# ESP_CAM_VVN.net
KiCad netlist of a schematic drawn in EAGLE
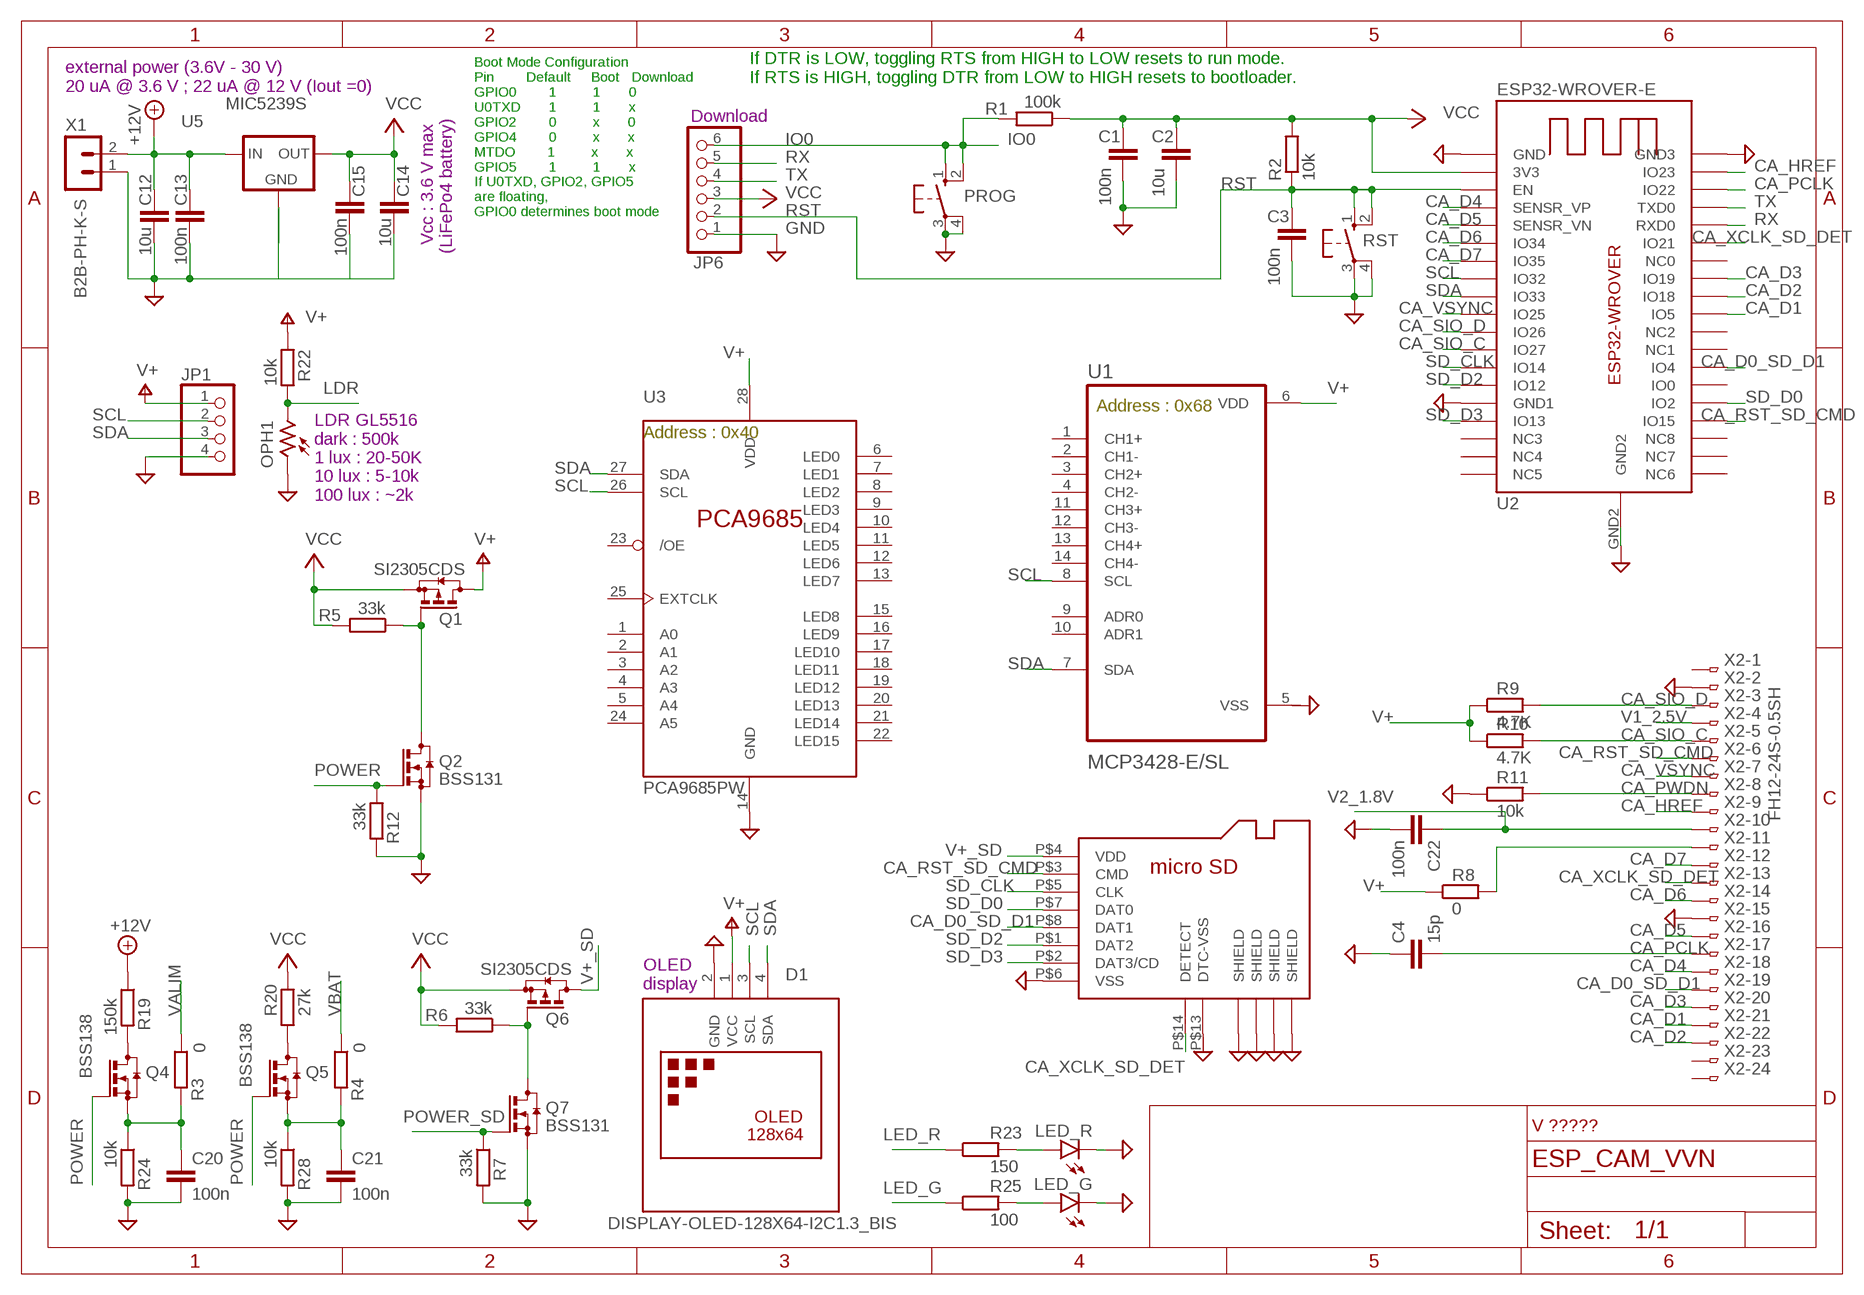
[diagram p0: schematic, sheet 1]

(export (version "E")
  (design (tool "Eeschema 10.0.6"))
  (components
    (comp (ref "C1")
      (value "100n")
      (footprint "eagle-import:C1206")
      (libsource (lib "eagle-import") (part "CC1206"))
    )
    (comp (ref "C2")
      (value "10u")
      (footprint "eagle-import:C1210")
      (libsource (lib "eagle-import") (part "CC1210"))
    )
    (comp (ref "C3")
      (value "100n")
      (footprint "eagle-import:C1206")
      (libsource (lib "eagle-import") (part "CC1206"))
    )
    (comp (ref "C4")
      (value "15p")
      (footprint "eagle-import:C1206")
      (libsource (lib "eagle-import") (part "CC1206"))
    )
    (comp (ref "C12")
      (value "10u")
      (footprint "eagle-import:C1210")
      (libsource (lib "eagle-import") (part "CC1210"))
    )
    (comp (ref "C13")
      (value "100n")
      (footprint "eagle-import:C1206")
      (libsource (lib "eagle-import") (part "CC1206"))
    )
    (comp (ref "C14")
      (value "10u")
      (footprint "eagle-import:C1210")
      (libsource (lib "eagle-import") (part "CC1210"))
    )
    (comp (ref "C15")
      (value "100n")
      (footprint "eagle-import:C1206")
      (libsource (lib "eagle-import") (part "CC1206"))
    )
    (comp (ref "C20")
      (value "100n")
      (footprint "eagle-import:C1206")
      (libsource (lib "eagle-import") (part "CC1206"))
    )
    (comp (ref "C21")
      (value "100n")
      (footprint "eagle-import:C1206")
      (libsource (lib "eagle-import") (part "CC1206"))
    )
    (comp (ref "C22")
      (value "100n")
      (footprint "eagle-import:C1206")
      (libsource (lib "eagle-import") (part "CC1206"))
    )
    (comp (ref "D1")
      (value "DISPLAY-OLED-128X64-I2C1.3_BIS")
      (footprint "eagle-import:DISPLAY-OLED-128X64-1.3-I2C_BIS")
      (libsource (lib "eagle-import") (part "DISPLAY-OLED-128X64-I2C1.3_BIS"))
    )
    (comp (ref "JP1")
      (value "PINHD-1X4")
      (footprint "eagle-import:1X04")
      (libsource (lib "eagle-import") (part "PINHD-1X4"))
    )
    (comp (ref "JP6")
      (value "PINHD-1X6")
      (footprint "eagle-import:1X06")
      (libsource (lib "eagle-import") (part "PINHD-1X6"))
    )
    (comp (ref "LED_G")
      (value "LEDSMT1206")
      (footprint "eagle-import:1206")
      (libsource (lib "eagle-import") (part "LEDSMT1206"))
    )
    (comp (ref "LED_R")
      (value "LEDSMT1206")
      (footprint "eagle-import:1206")
      (libsource (lib "eagle-import") (part "LEDSMT1206"))
    )
    (comp (ref "OPH1")
      (value "VT93N2")
      (footprint "eagle-import:VT900")
      (libsource (lib "eagle-import") (part "VT93N2"))
    )
    (comp (ref "PROG")
      (value "10-XX")
      (footprint "eagle-import:B3F-10XX")
      (fields (field (name "MPN") "B3F-1000"))
      (libsource (lib "eagle-import") (part "10-XX"))
    )
    (comp (ref "Q1")
      (value "SI2305CDS")
      (footprint "eagle-import:SOT23")
      (libsource (lib "eagle-import") (part "SI2305CDS"))
    )
    (comp (ref "Q2")
      (value "BSS131")
      (footprint "eagle-import:SOT23")
      (libsource (lib "eagle-import") (part "BSS131"))
    )
    (comp (ref "Q4")
      (value "BSS138")
      (footprint "eagle-import:SOT23")
      (libsource (lib "eagle-import") (part "BSS138"))
    )
    (comp (ref "Q5")
      (value "BSS138")
      (footprint "eagle-import:SOT23")
      (libsource (lib "eagle-import") (part "BSS138"))
    )
    (comp (ref "Q6")
      (value "SI2305CDS")
      (footprint "eagle-import:SOT23")
      (libsource (lib "eagle-import") (part "SI2305CDS"))
    )
    (comp (ref "Q7")
      (value "BSS131")
      (footprint "eagle-import:SOT23")
      (libsource (lib "eagle-import") (part "BSS131"))
    )
    (comp (ref "R1")
      (value "100k")
      (footprint "eagle-import:R1206")
      (libsource (lib "eagle-import") (part "RR1206"))
    )
    (comp (ref "R2")
      (value "10k")
      (footprint "eagle-import:R1206")
      (libsource (lib "eagle-import") (part "RR1206"))
    )
    (comp (ref "R3")
      (value "0")
      (footprint "eagle-import:R1206")
      (libsource (lib "eagle-import") (part "RR1206"))
    )
    (comp (ref "R4")
      (value "0")
      (footprint "eagle-import:R1206")
      (libsource (lib "eagle-import") (part "RR1206"))
    )
    (comp (ref "R5")
      (value "33k")
      (footprint "eagle-import:R1206")
      (libsource (lib "eagle-import") (part "RR1206"))
    )
    (comp (ref "R6")
      (value "33k")
      (footprint "eagle-import:R1206")
      (libsource (lib "eagle-import") (part "RR1206"))
    )
    (comp (ref "R7")
      (value "33k")
      (footprint "eagle-import:R1206")
      (libsource (lib "eagle-import") (part "RR1206"))
    )
    (comp (ref "R8")
      (value "0")
      (footprint "eagle-import:R1206")
      (libsource (lib "eagle-import") (part "RR1206"))
    )
    (comp (ref "R9")
      (value "4.7K")
      (footprint "eagle-import:R1206")
      (libsource (lib "eagle-import") (part "RR1206"))
    )
    (comp (ref "R10")
      (value "4.7K")
      (footprint "eagle-import:R1206")
      (libsource (lib "eagle-import") (part "RR1206"))
    )
    (comp (ref "R11")
      (value "10k")
      (footprint "eagle-import:R1206")
      (libsource (lib "eagle-import") (part "RR1206"))
    )
    (comp (ref "R12")
      (value "33k")
      (footprint "eagle-import:R1206")
      (libsource (lib "eagle-import") (part "RR1206"))
    )
    (comp (ref "R19")
      (value "150k")
      (footprint "eagle-import:R1206")
      (libsource (lib "eagle-import") (part "RR1206"))
    )
    (comp (ref "R20")
      (value "27k")
      (footprint "eagle-import:R1206")
      (libsource (lib "eagle-import") (part "RR1206"))
    )
    (comp (ref "R22")
      (value "10k")
      (footprint "eagle-import:R1206")
      (libsource (lib "eagle-import") (part "RR1206"))
    )
    (comp (ref "R23")
      (value "150")
      (footprint "eagle-import:R1206")
      (libsource (lib "eagle-import") (part "RR1206"))
    )
    (comp (ref "R24")
      (value "10k")
      (footprint "eagle-import:R1206")
      (libsource (lib "eagle-import") (part "RR1206"))
    )
    (comp (ref "R25")
      (value "100")
      (footprint "eagle-import:R1206")
      (libsource (lib "eagle-import") (part "RR1206"))
    )
    (comp (ref "R28")
      (value "10k")
      (footprint "eagle-import:R1206")
      (libsource (lib "eagle-import") (part "RR1206"))
    )
    (comp (ref "RST")
      (value "10-XX")
      (footprint "eagle-import:B3F-10XX")
      (fields (field (name "MPN") "B3F-1000"))
      (libsource (lib "eagle-import") (part "10-XX"))
    )
    (comp (ref "SD1")
      (value "MICRO-SD-8")
      (footprint "eagle-import:MICROSDMOLEX")
      (libsource (lib "eagle-import") (part "MICRO-SD-8"))
    )
    (comp (ref "U1")
      (value "MCP3428-E/SL")
      (footprint "eagle-import:SOIC127P600X175-14N")
      (fields (field (name "MF") "Microchip"))
      (libsource (lib "eagle-import") (part "MCP3428-E/SL"))
    )
    (comp (ref "U2")
      (value "ESP32-WROVER-E")
      (footprint "eagle-import:ESP32-WROVER")
      (libsource (lib "eagle-import") (part "ESP32-WROVER-E"))
    )
    (comp (ref "U3")
      (value "PCA9685PW")
      (footprint "eagle-import:TSSOP28")
      (libsource (lib "eagle-import") (part "PCA9685PW"))
    )
    (comp (ref "U5")
      (value "MIC5239S")
      (footprint "eagle-import:SOT223")
      (libsource (lib "eagle-import") (part "MIC5239S"))
    )
    (comp (ref "X1")
      (value "B2B-PH-K-S")
      (footprint "eagle-import:B2B-PH-K-S")
      (libsource (lib "eagle-import") (part "B2B-PH-K-S"))
    )
    (comp (ref "X2")
      (value "FH12-24S-0.5SH")
      (footprint "eagle-import:FH12-24S-0.5SH")
      (fields (field (name "MPN") "FH12-24S-0.5SH(55)"))
      (libsource (lib "eagle-import") (part "FH12-24S-0.5SH"))
    )
  )
  (nets
    (net (code "1") (name "+12V") (class "Default")
      (node (ref "C12") (pin "1") (pinfunction "1_1") (pintype "passive"))
      (node (ref "C13") (pin "1") (pinfunction "1_1") (pintype "passive"))
      (node (ref "R19") (pin "1") (pinfunction "1_1") (pintype "passive"))
      (node (ref "U5") (pin "1") (pinfunction "IN_1") (pintype "input"))
      (node (ref "X1") (pin "2") (pinfunction "2_2") (pintype "passive"))
    )
    (net (code "2") (name "/CA_D0_SD_D1") (class "Default")
      (node (ref "SD1") (pin "P$8") (pinfunction "DAT1_P$8") (pintype "bidirectional"))
      (node (ref "U2") (pin "IO4") (pinfunction "IO4_IO4") (pintype "bidirectional"))
      (node (ref "X2") (pin "19") (pinfunction "1_19") (pintype "passive"))
    )
    (net (code "3") (name "/CA_D1") (class "Default")
      (node (ref "U2") (pin "IO5") (pinfunction "IO5_IO5") (pintype "bidirectional"))
      (node (ref "X2") (pin "21") (pinfunction "1_21") (pintype "passive"))
    )
    (net (code "4") (name "/CA_D2") (class "Default")
      (node (ref "U2") (pin "IO18") (pinfunction "IO18_IO18") (pintype "bidirectional"))
      (node (ref "X2") (pin "22") (pinfunction "1_22") (pintype "passive"))
    )
    (net (code "5") (name "/CA_D3") (class "Default")
      (node (ref "U2") (pin "IO19") (pinfunction "IO19_IO19") (pintype "bidirectional"))
      (node (ref "X2") (pin "20") (pinfunction "1_20") (pintype "passive"))
    )
    (net (code "6") (name "/CA_D4") (class "Default")
      (node (ref "U2") (pin "SENSOR_VP") (pinfunction "SENSR_VP_SENSOR_VP") (pintype "bidirectional"))
      (node (ref "X2") (pin "18") (pinfunction "1_18") (pintype "passive"))
    )
    (net (code "7") (name "/CA_D5") (class "Default")
      (node (ref "U2") (pin "SENSOR_VN") (pinfunction "SENSR_VN_SENSOR_VN") (pintype "bidirectional"))
      (node (ref "X2") (pin "16") (pinfunction "1_16") (pintype "passive"))
    )
    (net (code "8") (name "/CA_D6") (class "Default")
      (node (ref "U2") (pin "IO34") (pinfunction "IO34_IO34") (pintype "bidirectional"))
      (node (ref "X2") (pin "14") (pinfunction "1_14") (pintype "passive"))
    )
    (net (code "9") (name "/CA_D7") (class "Default")
      (node (ref "U2") (pin "IO35") (pinfunction "IO35_IO35") (pintype "bidirectional"))
      (node (ref "X2") (pin "12") (pinfunction "1_12") (pintype "passive"))
    )
    (net (code "10") (name "/CA_HREF") (class "Default")
      (node (ref "U2") (pin "IO23") (pinfunction "IO23_IO23") (pintype "bidirectional"))
      (node (ref "X2") (pin "9") (pinfunction "1_9") (pintype "passive"))
    )
    (net (code "11") (name "/CA_PCLK") (class "Default")
      (node (ref "C4") (pin "2") (pinfunction "2_2") (pintype "passive"))
      (node (ref "U2") (pin "IO22") (pinfunction "IO22_IO22") (pintype "bidirectional"))
      (node (ref "X2") (pin "17") (pinfunction "1_17") (pintype "passive"))
    )
    (net (code "12") (name "/CA_PWDN") (class "Default")
      (node (ref "R11") (pin "2") (pinfunction "2_2") (pintype "passive"))
      (node (ref "X2") (pin "8") (pinfunction "1_8") (pintype "passive"))
    )
    (net (code "13") (name "/CA_RST_SD_CMD") (class "Default")
      (node (ref "SD1") (pin "P$3") (pinfunction "CMD_P$3") (pintype "bidirectional"))
      (node (ref "U2") (pin "IO15") (pinfunction "IO15_IO15") (pintype "bidirectional"))
      (node (ref "X2") (pin "6") (pinfunction "1_6") (pintype "passive"))
    )
    (net (code "14") (name "/CA_SIO_C") (class "Default")
      (node (ref "R10") (pin "2") (pinfunction "2_2") (pintype "passive"))
      (node (ref "U2") (pin "IO27") (pinfunction "IO27_IO27") (pintype "bidirectional"))
      (node (ref "X2") (pin "5") (pinfunction "1_5") (pintype "passive"))
    )
    (net (code "15") (name "/CA_SIO_D") (class "Default")
      (node (ref "R9") (pin "2") (pinfunction "2_2") (pintype "passive"))
      (node (ref "U2") (pin "IO26") (pinfunction "IO26_IO26") (pintype "bidirectional"))
      (node (ref "X2") (pin "3") (pinfunction "1_3") (pintype "passive"))
    )
    (net (code "16") (name "/CA_VSYNC") (class "Default")
      (node (ref "U2") (pin "IO25") (pinfunction "IO25_IO25") (pintype "bidirectional"))
      (node (ref "X2") (pin "7") (pinfunction "1_7") (pintype "passive"))
    )
    (net (code "17") (name "/CA_XCLK_SD_DET") (class "Default")
      (node (ref "SD1") (pin "P$14") (pinfunction "DETECT_P$14") (pintype "power_in"))
      (node (ref "U2") (pin "IO21") (pinfunction "IO21_IO21") (pintype "bidirectional"))
      (node (ref "X2") (pin "13") (pinfunction "1_13") (pintype "passive"))
    )
    (net (code "18") (name "/IO0") (class "Default")
      (node (ref "JP6") (pin "6") (pinfunction "6_6") (pintype "passive"))
      (node (ref "PROG") (pin "1") (pinfunction "S_1") (pintype "passive"))
      (node (ref "PROG") (pin "2") (pinfunction "S1_2") (pintype "passive"))
      (node (ref "R1") (pin "2") (pinfunction "2_2") (pintype "passive"))
    )
    (net (code "19") (name "/LDR") (class "Default")
      (node (ref "OPH1") (pin "2") (pinfunction "2_2") (pintype "passive"))
      (node (ref "R22") (pin "2") (pinfunction "2_2") (pintype "passive"))
    )
    (net (code "20") (name "/LED_G") (class "Default")
      (node (ref "R25") (pin "1") (pinfunction "1_1") (pintype "passive"))
    )
    (net (code "21") (name "/LED_R") (class "Default")
      (node (ref "R23") (pin "1") (pinfunction "1_1") (pintype "passive"))
    )
    (net (code "22") (name "/POWER") (class "Default")
      (node (ref "Q2") (pin "1") (pinfunction "G_1") (pintype "passive"))
      (node (ref "Q4") (pin "1") (pinfunction "G_1") (pintype "passive"))
      (node (ref "Q5") (pin "1") (pinfunction "G_1") (pintype "passive"))
      (node (ref "R12") (pin "1") (pinfunction "1_1") (pintype "passive"))
    )
    (net (code "23") (name "/POWER_SD") (class "Default")
      (node (ref "Q7") (pin "1") (pinfunction "G_1") (pintype "passive"))
      (node (ref "R7") (pin "1") (pinfunction "1_1") (pintype "passive"))
    )
    (net (code "24") (name "/RST") (class "Default")
      (node (ref "C3") (pin "1") (pinfunction "1_1") (pintype "passive"))
      (node (ref "JP6") (pin "2") (pinfunction "2_2") (pintype "passive"))
      (node (ref "R2") (pin "1") (pinfunction "1_1") (pintype "passive"))
      (node (ref "RST") (pin "1") (pinfunction "S_1") (pintype "passive"))
      (node (ref "RST") (pin "2") (pinfunction "S1_2") (pintype "passive"))
      (node (ref "U2") (pin "EN") (pinfunction "EN_EN") (pintype "bidirectional"))
    )
    (net (code "25") (name "/RX") (class "Default")
      (node (ref "JP6") (pin "5") (pinfunction "5_5") (pintype "passive"))
      (node (ref "U2") (pin "RXD0") (pinfunction "RXD0_RXD0") (pintype "bidirectional"))
    )
    (net (code "26") (name "/SCL") (class "Default")
      (node (ref "D1") (pin "3") (pinfunction "SCL_3") (pintype "bidirectional"))
      (node (ref "JP1") (pin "2") (pinfunction "2_2") (pintype "passive"))
      (node (ref "U1") (pin "8") (pinfunction "SCL_8") (pintype "input"))
      (node (ref "U2") (pin "IO32") (pinfunction "IO32_IO32") (pintype "bidirectional"))
      (node (ref "U3") (pin "26") (pinfunction "SCL_26") (pintype "bidirectional"))
    )
    (net (code "27") (name "/SDA") (class "Default")
      (node (ref "D1") (pin "4") (pinfunction "SDA_4") (pintype "bidirectional"))
      (node (ref "JP1") (pin "3") (pinfunction "3_3") (pintype "passive"))
      (node (ref "U1") (pin "7") (pinfunction "SDA_7") (pintype "bidirectional"))
      (node (ref "U2") (pin "IO33") (pinfunction "IO33_IO33") (pintype "bidirectional"))
      (node (ref "U3") (pin "27") (pinfunction "SDA_27") (pintype "bidirectional"))
    )
    (net (code "28") (name "/SD_CLK") (class "Default")
      (node (ref "SD1") (pin "P$5") (pinfunction "CLK_P$5") (pintype "bidirectional"))
      (node (ref "U2") (pin "IO14") (pinfunction "IO14_IO14") (pintype "bidirectional"))
    )
    (net (code "29") (name "/SD_D0") (class "Default")
      (node (ref "SD1") (pin "P$7") (pinfunction "DAT0_P$7") (pintype "bidirectional"))
      (node (ref "U2") (pin "IO2") (pinfunction "IO2_IO2") (pintype "bidirectional"))
    )
    (net (code "30") (name "/SD_D2") (class "Default")
      (node (ref "SD1") (pin "P$1") (pinfunction "DAT2_P$1") (pintype "bidirectional"))
      (node (ref "U2") (pin "IO12") (pinfunction "IO12_IO12") (pintype "bidirectional"))
    )
    (net (code "31") (name "/SD_D3") (class "Default")
      (node (ref "SD1") (pin "P$2") (pinfunction "DAT3/CD_P$2") (pintype "bidirectional"))
      (node (ref "U2") (pin "IO13") (pinfunction "IO13_IO13") (pintype "bidirectional"))
    )
    (net (code "32") (name "/TX") (class "Default")
      (node (ref "JP6") (pin "4") (pinfunction "4_4") (pintype "passive"))
      (node (ref "U2") (pin "TXD0") (pinfunction "TXD0_TXD0") (pintype "bidirectional"))
    )
    (net (code "33") (name "/V+_SD") (class "Default")
      (node (ref "Q6") (pin "3") (pinfunction "D_3") (pintype "passive"))
      (node (ref "SD1") (pin "P$4") (pinfunction "VDD_P$4") (pintype "power_in"))
    )
    (net (code "34") (name "/V1_2.5V") (class "Default")
      (node (ref "X2") (pin "4") (pinfunction "1_4") (pintype "passive"))
    )
    (net (code "35") (name "/V2_1.8V") (class "Default")
      (node (ref "C22") (pin "1") (pinfunction "1_1") (pintype "passive"))
      (node (ref "X2") (pin "10") (pinfunction "1_10") (pintype "passive"))
    )
    (net (code "36") (name "/VALIM") (class "Default")
      (node (ref "R3") (pin "1") (pinfunction "1_1") (pintype "passive"))
    )
    (net (code "37") (name "/VBAT") (class "Default")
      (node (ref "R4") (pin "1") (pinfunction "1_1") (pintype "passive"))
    )
    (net (code "38") (name "/VSS") (class "Default")
      (node (ref "U1") (pin "5") (pinfunction "VSS_5") (pintype "power_in"))
    )
    (net (code "39") (name "GND") (class "Default")
      (node (ref "C1") (pin "2") (pinfunction "2_2") (pintype "passive"))
      (node (ref "C12") (pin "2") (pinfunction "2_2") (pintype "passive"))
      (node (ref "C13") (pin "2") (pinfunction "2_2") (pintype "passive"))
      (node (ref "C14") (pin "2") (pinfunction "2_2") (pintype "passive"))
      (node (ref "C15") (pin "2") (pinfunction "2_2") (pintype "passive"))
      (node (ref "C2") (pin "2") (pinfunction "2_2") (pintype "passive"))
      (node (ref "C20") (pin "2") (pinfunction "2_2") (pintype "passive"))
      (node (ref "C21") (pin "2") (pinfunction "2_2") (pintype "passive"))
      (node (ref "C22") (pin "2") (pinfunction "2_2") (pintype "passive"))
      (node (ref "C3") (pin "2") (pinfunction "2_2") (pintype "passive"))
      (node (ref "C4") (pin "1") (pinfunction "1_1") (pintype "passive"))
      (node (ref "D1") (pin "2") (pinfunction "GND_2") (pintype "power_in"))
      (node (ref "JP1") (pin "4") (pinfunction "4_4") (pintype "passive"))
      (node (ref "JP6") (pin "1") (pinfunction "1_1") (pintype "passive"))
      (node (ref "LED_G") (pin "C") (pinfunction "C_C") (pintype "passive"))
      (node (ref "LED_R") (pin "C") (pinfunction "C_C") (pintype "passive"))
      (node (ref "OPH1") (pin "1") (pinfunction "1_1") (pintype "passive"))
      (node (ref "PROG") (pin "3") (pinfunction "P_3") (pintype "passive"))
      (node (ref "PROG") (pin "4") (pinfunction "P1_4") (pintype "passive"))
      (node (ref "Q2") (pin "2") (pinfunction "S_2") (pintype "passive"))
      (node (ref "Q7") (pin "2") (pinfunction "S_2") (pintype "passive"))
      (node (ref "R11") (pin "1") (pinfunction "1_1") (pintype "passive"))
      (node (ref "R12") (pin "2") (pinfunction "2_2") (pintype "passive"))
      (node (ref "R24") (pin "2") (pinfunction "2_2") (pintype "passive"))
      (node (ref "R28") (pin "2") (pinfunction "2_2") (pintype "passive"))
      (node (ref "R7") (pin "2") (pinfunction "2_2") (pintype "passive"))
      (node (ref "RST") (pin "3") (pinfunction "P_3") (pintype "passive"))
      (node (ref "RST") (pin "4") (pinfunction "P1_4") (pintype "passive"))
      (node (ref "SD1") (pin "P$10") (pinfunction "SHIELD_P$10") (pintype "power_in"))
      (node (ref "SD1") (pin "P$11") (pinfunction "SHIELD_P$11") (pintype "power_in"))
      (node (ref "SD1") (pin "P$12") (pinfunction "SHIELD_P$12") (pintype "power_in"))
      (node (ref "SD1") (pin "P$13") (pinfunction "DTC-VSS_P$13") (pintype "power_in"))
      (node (ref "SD1") (pin "P$6") (pinfunction "VSS_P$6") (pintype "power_in"))
      (node (ref "SD1") (pin "P$9") (pinfunction "SHIELD_P$9") (pintype "power_in"))
      (node (ref "U2") (pin "GND") (pinfunction "GND_GND") (pintype "bidirectional"))
      (node (ref "U2") (pin "GND1") (pinfunction "GND1_GND1") (pintype "bidirectional"))
      (node (ref "U2") (pin "GND2") (pinfunction "GND2_GND2") (pintype "bidirectional"))
      (node (ref "U2") (pin "GND3") (pinfunction "GND3_GND3") (pintype "bidirectional"))
      (node (ref "U3") (pin "14") (pinfunction "GND_14") (pintype "power_in"))
      (node (ref "U5") (pin "2") (pinfunction "GND_2") (pintype "passive"))
      (node (ref "U5") (pin "4") (pinfunction "GND_4") (pintype "passive"))
      (node (ref "X1") (pin "1") (pinfunction "1_1") (pintype "passive"))
      (node (ref "X2") (pin "15") (pinfunction "1_15") (pintype "passive"))
      (node (ref "X2") (pin "2") (pinfunction "1_2") (pintype "passive"))
    )
    (net (code "40") (name "Net-(LED_G-PadA)") (class "Default")
      (node (ref "LED_G") (pin "A") (pinfunction "A_A") (pintype "passive"))
      (node (ref "R25") (pin "2") (pinfunction "2_2") (pintype "passive"))
    )
    (net (code "41") (name "Net-(LED_R-PadA)") (class "Default")
      (node (ref "LED_R") (pin "A") (pinfunction "A_A") (pintype "passive"))
      (node (ref "R23") (pin "2") (pinfunction "2_2") (pintype "passive"))
    )
    (net (code "42") (name "Net-(Q1-G)") (class "Default")
      (node (ref "Q1") (pin "1") (pinfunction "G_1") (pintype "passive"))
      (node (ref "Q2") (pin "3") (pinfunction "D_3") (pintype "passive"))
      (node (ref "R5") (pin "1") (pinfunction "1_1") (pintype "passive"))
    )
    (net (code "43") (name "Net-(Q4-D)") (class "Default")
      (node (ref "Q4") (pin "3") (pinfunction "D_3") (pintype "passive"))
      (node (ref "R19") (pin "2") (pinfunction "2_2") (pintype "passive"))
    )
    (net (code "44") (name "Net-(Q4-S)") (class "Default")
      (node (ref "C20") (pin "1") (pinfunction "1_1") (pintype "passive"))
      (node (ref "Q4") (pin "2") (pinfunction "S_2") (pintype "passive"))
      (node (ref "R24") (pin "1") (pinfunction "1_1") (pintype "passive"))
      (node (ref "R3") (pin "2") (pinfunction "2_2") (pintype "passive"))
    )
    (net (code "45") (name "Net-(Q5-D)") (class "Default")
      (node (ref "Q5") (pin "3") (pinfunction "D_3") (pintype "passive"))
      (node (ref "R20") (pin "1") (pinfunction "1_1") (pintype "passive"))
    )
    (net (code "46") (name "Net-(Q5-S)") (class "Default")
      (node (ref "C21") (pin "1") (pinfunction "1_1") (pintype "passive"))
      (node (ref "Q5") (pin "2") (pinfunction "S_2") (pintype "passive"))
      (node (ref "R28") (pin "1") (pinfunction "1_1") (pintype "passive"))
      (node (ref "R4") (pin "2") (pinfunction "2_2") (pintype "passive"))
    )
    (net (code "47") (name "Net-(Q6-G)") (class "Default")
      (node (ref "Q6") (pin "1") (pinfunction "G_1") (pintype "passive"))
      (node (ref "Q7") (pin "3") (pinfunction "D_3") (pintype "passive"))
      (node (ref "R6") (pin "1") (pinfunction "1_1") (pintype "passive"))
    )
    (net (code "48") (name "Net-(X2C-1)") (class "Default")
      (node (ref "R8") (pin "2") (pinfunction "2_2") (pintype "passive"))
      (node (ref "X2") (pin "11") (pinfunction "1_11") (pintype "passive"))
    )
    (net (code "49") (name "V+") (class "Default")
      (node (ref "D1") (pin "1") (pinfunction "VCC_1") (pintype "power_in"))
      (node (ref "JP1") (pin "1") (pinfunction "1_1") (pintype "passive"))
      (node (ref "Q1") (pin "3") (pinfunction "D_3") (pintype "passive"))
      (node (ref "R10") (pin "1") (pinfunction "1_1") (pintype "passive"))
      (node (ref "R22") (pin "1") (pinfunction "1_1") (pintype "passive"))
      (node (ref "R8") (pin "1") (pinfunction "1_1") (pintype "passive"))
      (node (ref "R9") (pin "1") (pinfunction "1_1") (pintype "passive"))
      (node (ref "U1") (pin "6") (pinfunction "VDD_6") (pintype "power_in"))
      (node (ref "U3") (pin "28") (pinfunction "VDD_28") (pintype "power_in"))
    )
    (net (code "50") (name "VCC") (class "Default")
      (node (ref "C1") (pin "1") (pinfunction "1_1") (pintype "passive"))
      (node (ref "C14") (pin "1") (pinfunction "1_1") (pintype "passive"))
      (node (ref "C15") (pin "1") (pinfunction "1_1") (pintype "passive"))
      (node (ref "C2") (pin "1") (pinfunction "1_1") (pintype "passive"))
      (node (ref "JP6") (pin "3") (pinfunction "3_3") (pintype "passive"))
      (node (ref "Q1") (pin "2") (pinfunction "S_2") (pintype "passive"))
      (node (ref "Q6") (pin "2") (pinfunction "S_2") (pintype "passive"))
      (node (ref "R1") (pin "1") (pinfunction "1_1") (pintype "passive"))
      (node (ref "R2") (pin "2") (pinfunction "2_2") (pintype "passive"))
      (node (ref "R20") (pin "2") (pinfunction "2_2") (pintype "passive"))
      (node (ref "R5") (pin "2") (pinfunction "2_2") (pintype "passive"))
      (node (ref "R6") (pin "2") (pinfunction "2_2") (pintype "passive"))
      (node (ref "U2") (pin "VDD33") (pinfunction "3V3_VDD33") (pintype "bidirectional"))
      (node (ref "U5") (pin "3") (pinfunction "OUT_3") (pintype "passive"))
    )
    (net (code "51") (name "unconnected-(U1-ADR0-Pad9)") (class "Default")
      (node (ref "U1") (pin "9") (pinfunction "ADR0_9") (pintype "bidirectional"))
    )
    (net (code "52") (name "unconnected-(U1-ADR1-Pad10)") (class "Default")
      (node (ref "U1") (pin "10") (pinfunction "ADR1_10") (pintype "bidirectional"))
    )
    (net (code "53") (name "unconnected-(U1-CH1+-Pad1)") (class "Default")
      (node (ref "U1") (pin "1") (pinfunction "CH1+_1") (pintype "input"))
    )
    (net (code "54") (name "unconnected-(U1-CH1--Pad2)") (class "Default")
      (node (ref "U1") (pin "2") (pinfunction "CH1-_2") (pintype "input"))
    )
    (net (code "55") (name "unconnected-(U1-CH2+-Pad3)") (class "Default")
      (node (ref "U1") (pin "3") (pinfunction "CH2+_3") (pintype "input"))
    )
    (net (code "56") (name "unconnected-(U1-CH2--Pad4)") (class "Default")
      (node (ref "U1") (pin "4") (pinfunction "CH2-_4") (pintype "input"))
    )
    (net (code "57") (name "unconnected-(U1-CH3+-Pad11)") (class "Default")
      (node (ref "U1") (pin "11") (pinfunction "CH3+_11") (pintype "input"))
    )
    (net (code "58") (name "unconnected-(U1-CH3--Pad12)") (class "Default")
      (node (ref "U1") (pin "12") (pinfunction "CH3-_12") (pintype "input"))
    )
    (net (code "59") (name "unconnected-(U1-CH4+-Pad13)") (class "Default")
      (node (ref "U1") (pin "13") (pinfunction "CH4+_13") (pintype "input"))
    )
    (net (code "60") (name "unconnected-(U1-CH4--Pad14)") (class "Default")
      (node (ref "U1") (pin "14") (pinfunction "CH4-_14") (pintype "input"))
    )
    (net (code "61") (name "unconnected-(U2-NC3-PadCLK)") (class "Default")
      (node (ref "U2") (pin "CLK") (pinfunction "NC3_CLK") (pintype "bidirectional"))
    )
    (net (code "62") (name "unconnected-(U2-NC4-PadCMD)") (class "Default")
      (node (ref "U2") (pin "CMD") (pinfunction "NC4_CMD") (pintype "bidirectional"))
    )
    (net (code "63") (name "unconnected-(U2-NC5-PadSD0)") (class "Default")
      (node (ref "U2") (pin "SD0") (pinfunction "NC5_SD0") (pintype "bidirectional"))
    )
    (net (code "64") (name "unconnected-(U2-NC6-PadSD1)") (class "Default")
      (node (ref "U2") (pin "SD1") (pinfunction "NC6_SD1") (pintype "bidirectional"))
    )
    (net (code "65") (name "unconnected-(U2-NC7-PadSD2)") (class "Default")
      (node (ref "U2") (pin "SD2") (pinfunction "NC7_SD2") (pintype "bidirectional"))
    )
    (net (code "66") (name "unconnected-(U2-NC8-PadSD3)") (class "Default")
      (node (ref "U2") (pin "SD3") (pinfunction "NC8_SD3") (pintype "bidirectional"))
    )
    (net (code "67") (name "unconnected-(U2-PadIO0)") (class "Default")
      (node (ref "U2") (pin "IO0") (pinfunction "IO0_IO0") (pintype "bidirectional"))
    )
    (net (code "68") (name "unconnected-(U2-PadNC0)") (class "Default")
      (node (ref "U2") (pin "NC0") (pinfunction "NC0_NC0") (pintype "bidirectional"))
    )
    (net (code "69") (name "unconnected-(U2-PadNC1)") (class "Default")
      (node (ref "U2") (pin "NC1") (pinfunction "NC1_NC1") (pintype "bidirectional"))
    )
    (net (code "70") (name "unconnected-(U2-PadNC2)") (class "Default")
      (node (ref "U2") (pin "NC2") (pinfunction "NC2_NC2") (pintype "bidirectional"))
    )
    (net (code "71") (name "unconnected-(U3-A0-Pad1)") (class "Default")
      (node (ref "U3") (pin "1") (pinfunction "A0_1") (pintype "bidirectional"))
    )
    (net (code "72") (name "unconnected-(U3-A1-Pad2)") (class "Default")
      (node (ref "U3") (pin "2") (pinfunction "A1_2") (pintype "bidirectional"))
    )
    (net (code "73") (name "unconnected-(U3-A2-Pad3)") (class "Default")
      (node (ref "U3") (pin "3") (pinfunction "A2_3") (pintype "bidirectional"))
    )
    (net (code "74") (name "unconnected-(U3-A3-Pad4)") (class "Default")
      (node (ref "U3") (pin "4") (pinfunction "A3_4") (pintype "bidirectional"))
    )
    (net (code "75") (name "unconnected-(U3-A4-Pad5)") (class "Default")
      (node (ref "U3") (pin "5") (pinfunction "A4_5") (pintype "bidirectional"))
    )
    (net (code "76") (name "unconnected-(U3-A5-Pad24)") (class "Default")
      (node (ref "U3") (pin "24") (pinfunction "A5_24") (pintype "bidirectional"))
    )
    (net (code "77") (name "unconnected-(U3-EXTCLK-Pad25)") (class "Default")
      (node (ref "U3") (pin "25") (pinfunction "EXTCLK_25") (pintype "input"))
    )
    (net (code "78") (name "unconnected-(U3-LED0-Pad6)") (class "Default")
      (node (ref "U3") (pin "6") (pinfunction "LED0_6") (pintype "bidirectional"))
    )
    (net (code "79") (name "unconnected-(U3-LED1-Pad7)") (class "Default")
      (node (ref "U3") (pin "7") (pinfunction "LED1_7") (pintype "bidirectional"))
    )
    (net (code "80") (name "unconnected-(U3-LED2-Pad8)") (class "Default")
      (node (ref "U3") (pin "8") (pinfunction "LED2_8") (pintype "bidirectional"))
    )
    (net (code "81") (name "unconnected-(U3-LED3-Pad9)") (class "Default")
      (node (ref "U3") (pin "9") (pinfunction "LED3_9") (pintype "bidirectional"))
    )
    (net (code "82") (name "unconnected-(U3-LED4-Pad10)") (class "Default")
      (node (ref "U3") (pin "10") (pinfunction "LED4_10") (pintype "bidirectional"))
    )
    (net (code "83") (name "unconnected-(U3-LED5-Pad11)") (class "Default")
      (node (ref "U3") (pin "11") (pinfunction "LED5_11") (pintype "bidirectional"))
    )
    (net (code "84") (name "unconnected-(U3-LED6-Pad12)") (class "Default")
      (node (ref "U3") (pin "12") (pinfunction "LED6_12") (pintype "bidirectional"))
    )
    (net (code "85") (name "unconnected-(U3-LED7-Pad13)") (class "Default")
      (node (ref "U3") (pin "13") (pinfunction "LED7_13") (pintype "bidirectional"))
    )
    (net (code "86") (name "unconnected-(U3-LED8-Pad15)") (class "Default")
      (node (ref "U3") (pin "15") (pinfunction "LED8_15") (pintype "bidirectional"))
    )
    (net (code "87") (name "unconnected-(U3-LED9-Pad16)") (class "Default")
      (node (ref "U3") (pin "16") (pinfunction "LED9_16") (pintype "bidirectional"))
    )
    (net (code "88") (name "unconnected-(U3-LED10-Pad17)") (class "Default")
      (node (ref "U3") (pin "17") (pinfunction "LED10_17") (pintype "bidirectional"))
    )
    (net (code "89") (name "unconnected-(U3-LED11-Pad18)") (class "Default")
      (node (ref "U3") (pin "18") (pinfunction "LED11_18") (pintype "bidirectional"))
    )
    (net (code "90") (name "unconnected-(U3-LED12-Pad19)") (class "Default")
      (node (ref "U3") (pin "19") (pinfunction "LED12_19") (pintype "bidirectional"))
    )
    (net (code "91") (name "unconnected-(U3-LED13-Pad20)") (class "Default")
      (node (ref "U3") (pin "20") (pinfunction "LED13_20") (pintype "bidirectional"))
    )
    (net (code "92") (name "unconnected-(U3-LED14-Pad21)") (class "Default")
      (node (ref "U3") (pin "21") (pinfunction "LED14_21") (pintype "bidirectional"))
    )
    (net (code "93") (name "unconnected-(U3-LED15-Pad22)") (class "Default")
      (node (ref "U3") (pin "22") (pinfunction "LED15_22") (pintype "bidirectional"))
    )
    (net (code "94") (name "unconnected-(U3-{slash}OE-Pad23)") (class "Default")
      (node (ref "U3") (pin "23") (pinfunction "/OE_23") (pintype "bidirectional"))
    )
    (net (code "95") (name "unconnected-(X2-Pad1)") (class "Default")
      (node (ref "X2") (pin "1") (pinfunction "1_1") (pintype "passive"))
    )
    (net (code "96") (name "unconnected-(X2P-1-Pad23)") (class "Default")
      (node (ref "X2") (pin "23") (pinfunction "1_23") (pintype "passive"))
    )
    (net (code "97") (name "unconnected-(X2Q-1-Pad24)") (class "Default")
      (node (ref "X2") (pin "24") (pinfunction "1_24") (pintype "passive"))
    )
  )
)
